# LeftRightTurretLRUD.net
KiCad netlist of a schematic drawn in EAGLE
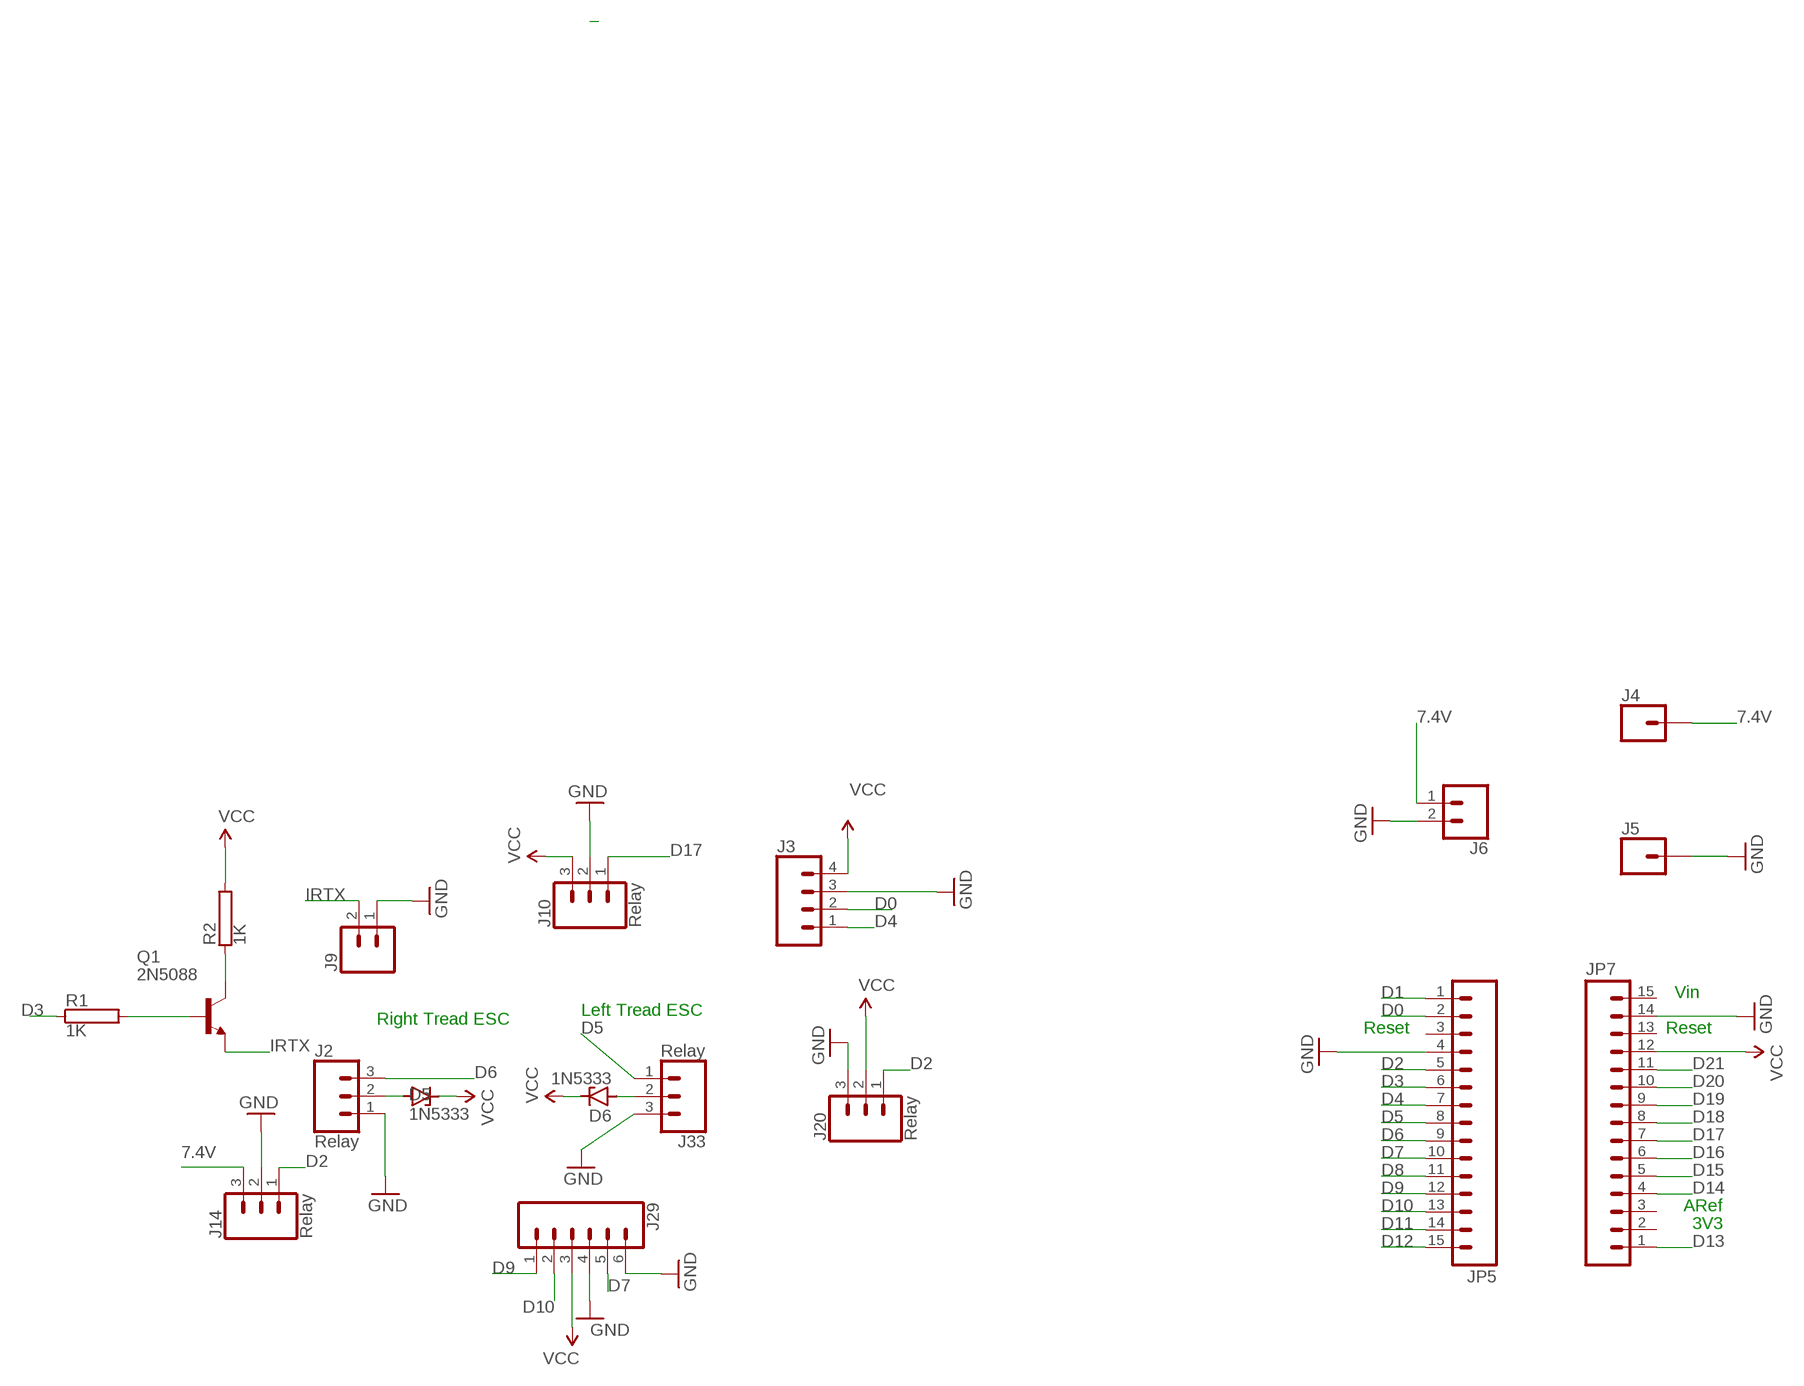
[diagram p0: schematic, sheet 1]

(export (version "E")
  (design (tool "Eeschema 10.0.6"))
  (components
    (comp (ref "D5")
      (value "1N5333")
      (footprint "eagle-import:C1702-15")
      (libsource (lib "eagle-import") (part "1N5333"))
    )
    (comp (ref "D6")
      (value "1N5333")
      (footprint "eagle-import:C1702-15")
      (libsource (lib "eagle-import") (part "1N5333"))
    )
    (comp (ref "J2")
      (value "Relay")
      (footprint "eagle-import:1X03")
      (libsource (lib "eagle-import") (part "CONN_03"))
    )
    (comp (ref "J3")
      (value "CONN_04")
      (footprint "eagle-import:1X04")
      (libsource (lib "eagle-import") (part "CONN_04"))
    )
    (comp (ref "J4")
      (value "CONN_01")
      (footprint "eagle-import:1X01")
      (libsource (lib "eagle-import") (part "CONN_01"))
    )
    (comp (ref "J5")
      (value "CONN_01")
      (footprint "eagle-import:1X01")
      (libsource (lib "eagle-import") (part "CONN_01"))
    )
    (comp (ref "J6")
      (value "CONN_02")
      (footprint "eagle-import:1X02")
      (libsource (lib "eagle-import") (part "CONN_02"))
    )
    (comp (ref "J9")
      (value "CONN_02")
      (footprint "eagle-import:1X02")
      (libsource (lib "eagle-import") (part "CONN_02"))
    )
    (comp (ref "J10")
      (value "Relay")
      (footprint "eagle-import:1X03")
      (libsource (lib "eagle-import") (part "CONN_03"))
    )
    (comp (ref "J14")
      (value "Relay")
      (footprint "eagle-import:1X03")
      (libsource (lib "eagle-import") (part "CONN_03"))
    )
    (comp (ref "J20")
      (value "Relay")
      (footprint "eagle-import:1X03")
      (libsource (lib "eagle-import") (part "CONN_03"))
    )
    (comp (ref "J29")
      (value "CONN_06NO_SILK_FEMALE_PTH")
      (footprint "eagle-import:1X06_NO_SILK")
      (libsource (lib "eagle-import") (part "CONN_06NO_SILK_FEMALE_PTH"))
    )
    (comp (ref "J33")
      (value "Relay")
      (footprint "eagle-import:1X03")
      (libsource (lib "eagle-import") (part "CONN_03"))
    )
    (comp (ref "JP5")
      (value "M15")
      (footprint "eagle-import:1X15@1")
      (libsource (lib "eagle-import") (part "M15"))
    )
    (comp (ref "JP7")
      (value "M15")
      (footprint "eagle-import:1X15@1")
      (libsource (lib "eagle-import") (part "M15"))
    )
    (comp (ref "Q1")
      (value "2N5088")
      (footprint "eagle-import:TO92")
      (libsource (lib "eagle-import") (part "2N5088"))
    )
    (comp (ref "R1")
      (value "1K")
      (footprint "eagle-import:CA0001")
      (libsource (lib "eagle-import") (part "RCA0001"))
    )
    (comp (ref "R2")
      (value "1K")
      (footprint "eagle-import:CA0001")
      (libsource (lib "eagle-import") (part "RCA0001"))
    )
  )
  (nets
    (net (code "1") (name "/7.4V") (class "Default")
      (node (ref "J14") (pin "3") (pinfunction "3_3") (pintype "passive"))
      (node (ref "J4") (pin "1") (pinfunction "1_1") (pintype "passive"))
      (node (ref "J6") (pin "1") (pinfunction "1_1") (pintype "passive"))
    )
    (net (code "2") (name "/D0") (class "Default")
      (node (ref "J3") (pin "2") (pinfunction "2_2") (pintype "passive"))
      (node (ref "JP5") (pin "2") (pinfunction "2_2") (pintype "passive"))
    )
    (net (code "3") (name "/D1") (class "Default")
      (node (ref "JP5") (pin "1") (pinfunction "1_1") (pintype "passive"))
    )
    (net (code "4") (name "/D2") (class "Default")
      (node (ref "J14") (pin "1") (pinfunction "1_1") (pintype "passive"))
      (node (ref "J20") (pin "1") (pinfunction "1_1") (pintype "passive"))
      (node (ref "JP5") (pin "5") (pinfunction "5_5") (pintype "passive"))
    )
    (net (code "5") (name "/D3") (class "Default")
      (node (ref "JP5") (pin "6") (pinfunction "6_6") (pintype "passive"))
      (node (ref "R1") (pin "1") (pinfunction "1_1") (pintype "passive"))
    )
    (net (code "6") (name "/D4") (class "Default")
      (node (ref "J3") (pin "1") (pinfunction "1_1") (pintype "passive"))
      (node (ref "JP5") (pin "7") (pinfunction "7_7") (pintype "passive"))
    )
    (net (code "7") (name "/D5") (class "Default")
      (node (ref "J33") (pin "1") (pinfunction "1_1") (pintype "passive"))
      (node (ref "JP5") (pin "8") (pinfunction "8_8") (pintype "passive"))
    )
    (net (code "8") (name "/D6") (class "Default")
      (node (ref "J2") (pin "3") (pinfunction "3_3") (pintype "passive"))
      (node (ref "JP5") (pin "9") (pinfunction "9_9") (pintype "passive"))
    )
    (net (code "9") (name "/D7") (class "Default")
      (node (ref "J29") (pin "5") (pinfunction "5_5") (pintype "passive"))
      (node (ref "JP5") (pin "10") (pinfunction "10_10") (pintype "passive"))
    )
    (net (code "10") (name "/D8") (class "Default")
      (node (ref "JP5") (pin "11") (pinfunction "11_11") (pintype "passive"))
    )
    (net (code "11") (name "/D9") (class "Default")
      (node (ref "J29") (pin "1") (pinfunction "1_1") (pintype "passive"))
      (node (ref "JP5") (pin "12") (pinfunction "12_12") (pintype "passive"))
    )
    (net (code "12") (name "/D10") (class "Default")
      (node (ref "J29") (pin "2") (pinfunction "2_2") (pintype "passive"))
      (node (ref "JP5") (pin "13") (pinfunction "13_13") (pintype "passive"))
    )
    (net (code "13") (name "/D11") (class "Default")
      (node (ref "JP5") (pin "14") (pinfunction "14_14") (pintype "passive"))
    )
    (net (code "14") (name "/D12") (class "Default")
      (node (ref "JP5") (pin "15") (pinfunction "15_15") (pintype "passive"))
    )
    (net (code "15") (name "/D13") (class "Default")
      (node (ref "JP7") (pin "1") (pinfunction "1_1") (pintype "passive"))
    )
    (net (code "16") (name "/D14") (class "Default")
      (node (ref "JP7") (pin "4") (pinfunction "4_4") (pintype "passive"))
    )
    (net (code "17") (name "/D15") (class "Default")
      (node (ref "JP7") (pin "5") (pinfunction "5_5") (pintype "passive"))
    )
    (net (code "18") (name "/D16") (class "Default")
      (node (ref "JP7") (pin "6") (pinfunction "6_6") (pintype "passive"))
    )
    (net (code "19") (name "/D17") (class "Default")
      (node (ref "J10") (pin "1") (pinfunction "1_1") (pintype "passive"))
      (node (ref "JP7") (pin "7") (pinfunction "7_7") (pintype "passive"))
    )
    (net (code "20") (name "/D18") (class "Default")
      (node (ref "JP7") (pin "8") (pinfunction "8_8") (pintype "passive"))
    )
    (net (code "21") (name "/D19") (class "Default")
      (node (ref "JP7") (pin "9") (pinfunction "9_9") (pintype "passive"))
    )
    (net (code "22") (name "/D20") (class "Default")
      (node (ref "JP7") (pin "10") (pinfunction "10_10") (pintype "passive"))
    )
    (net (code "23") (name "/D21") (class "Default")
      (node (ref "JP7") (pin "11") (pinfunction "11_11") (pintype "passive"))
    )
    (net (code "24") (name "/IRTX") (class "Default")
      (node (ref "J9") (pin "2") (pinfunction "2_2") (pintype "passive"))
      (node (ref "Q1") (pin "3") (pinfunction "E_3") (pintype "passive"))
    )
    (net (code "25") (name "GND") (class "Default")
      (node (ref "J10") (pin "2") (pinfunction "2_2") (pintype "passive"))
      (node (ref "J14") (pin "2") (pinfunction "2_2") (pintype "passive"))
      (node (ref "J2") (pin "1") (pinfunction "1_1") (pintype "passive"))
      (node (ref "J20") (pin "3") (pinfunction "3_3") (pintype "passive"))
      (node (ref "J29") (pin "4") (pinfunction "4_4") (pintype "passive"))
      (node (ref "J29") (pin "6") (pinfunction "6_6") (pintype "passive"))
      (node (ref "J3") (pin "3") (pinfunction "3_3") (pintype "passive"))
      (node (ref "J33") (pin "3") (pinfunction "3_3") (pintype "passive"))
      (node (ref "J5") (pin "1") (pinfunction "1_1") (pintype "passive"))
      (node (ref "J6") (pin "2") (pinfunction "2_2") (pintype "passive"))
      (node (ref "J9") (pin "1") (pinfunction "1_1") (pintype "passive"))
      (node (ref "JP5") (pin "4") (pinfunction "4_4") (pintype "passive"))
      (node (ref "JP7") (pin "14") (pinfunction "14_14") (pintype "passive"))
    )
    (net (code "26") (name "Net-(D5-PadA)") (class "Default")
      (node (ref "D5") (pin "A") (pinfunction "A_A") (pintype "passive"))
      (node (ref "J2") (pin "2") (pinfunction "2_2") (pintype "passive"))
    )
    (net (code "27") (name "Net-(D6-PadA)") (class "Default")
      (node (ref "D6") (pin "A") (pinfunction "A_A") (pintype "passive"))
      (node (ref "J33") (pin "2") (pinfunction "2_2") (pintype "passive"))
    )
    (net (code "28") (name "Net-(Q1-B)") (class "Default")
      (node (ref "Q1") (pin "2") (pinfunction "B_2") (pintype "passive"))
      (node (ref "R1") (pin "2") (pinfunction "2_2") (pintype "passive"))
    )
    (net (code "29") (name "Net-(Q1-C)") (class "Default")
      (node (ref "Q1") (pin "1") (pinfunction "C_1") (pintype "passive"))
      (node (ref "R2") (pin "1") (pinfunction "1_1") (pintype "passive"))
    )
    (net (code "30") (name "VCC") (class "Default")
      (node (ref "D5") (pin "C") (pinfunction "C_C") (pintype "passive"))
      (node (ref "D6") (pin "C") (pinfunction "C_C") (pintype "passive"))
      (node (ref "J10") (pin "3") (pinfunction "3_3") (pintype "passive"))
      (node (ref "J20") (pin "2") (pinfunction "2_2") (pintype "passive"))
      (node (ref "J29") (pin "3") (pinfunction "3_3") (pintype "passive"))
      (node (ref "J3") (pin "4") (pinfunction "4_4") (pintype "passive"))
      (node (ref "JP7") (pin "12") (pinfunction "12_12") (pintype "passive"))
      (node (ref "R2") (pin "2") (pinfunction "2_2") (pintype "passive"))
    )
    (net (code "31") (name "unconnected-(JP5-Pad3)") (class "Default")
      (node (ref "JP5") (pin "3") (pinfunction "3_3") (pintype "passive"))
    )
    (net (code "32") (name "unconnected-(JP7-Pad2)") (class "Default")
      (node (ref "JP7") (pin "2") (pinfunction "2_2") (pintype "passive"))
    )
    (net (code "33") (name "unconnected-(JP7-Pad3)") (class "Default")
      (node (ref "JP7") (pin "3") (pinfunction "3_3") (pintype "passive"))
    )
    (net (code "34") (name "unconnected-(JP7-Pad13)") (class "Default")
      (node (ref "JP7") (pin "13") (pinfunction "13_13") (pintype "passive"))
    )
    (net (code "35") (name "unconnected-(JP7-Pad15)") (class "Default")
      (node (ref "JP7") (pin "15") (pinfunction "15_15") (pintype "passive"))
    )
  )
)
